# EPS_MPPT_Y_EMI-Filter_In.net
KiCad netlist of a schematic drawn in Altium Designer
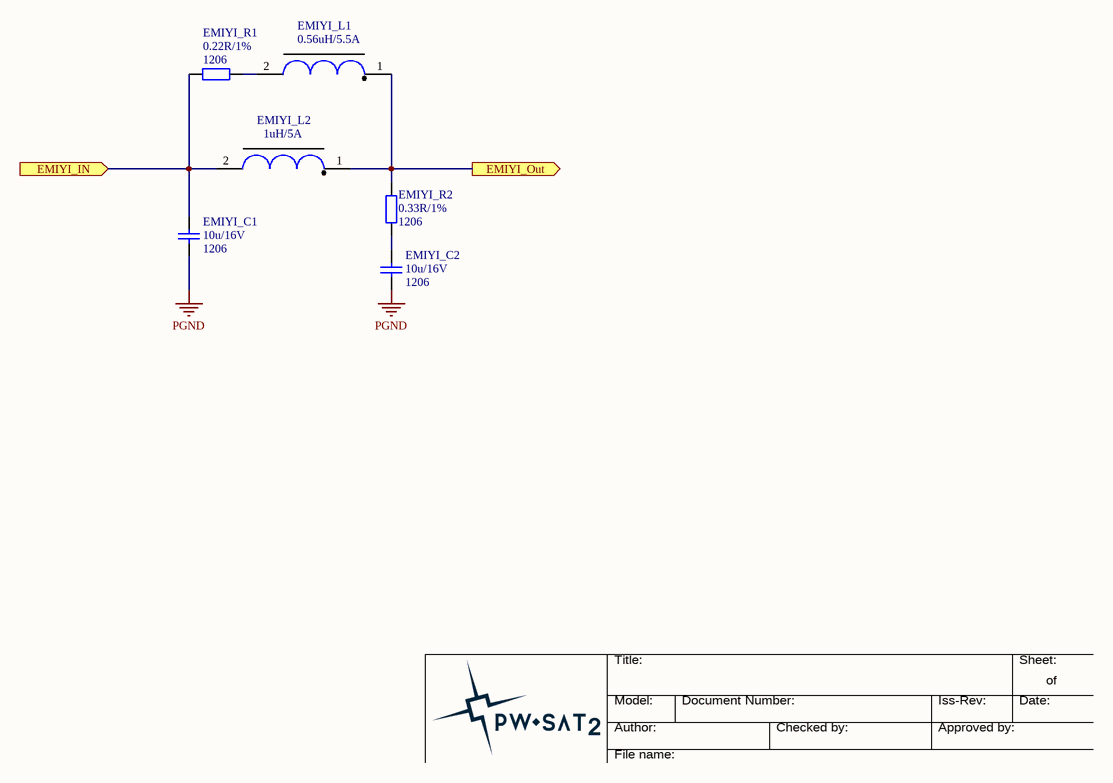
[diagram p0: EPS_MPPT_Y_EMI-Filter_In.SchDoc]

(export (version "E")
  (design (tool "Eeschema 10.0.6"))
  (components
    (comp (ref "EMIYI_C1")
      (value "10u/16V")
      (footprint "SMD_Capacitor_1206")
      (description "Ceramic Cap Kemet COTS 10u/16V X7R 1206")
      (fields
        (field (name "MANUFACTURERPARTNUMBER") "C1206T106K4RACTU")
        (field (name "MANUFACTURER") "Kemet")
        (field (name "PACKGE") "1206")
      )
      (libsource (lib "capacitors") (part "Cer_C1206T106K4RACTU"))
    )
    (comp (ref "EMIYI_C2")
      (value "10u/16V")
      (footprint "SMD_Capacitor_1206")
      (description "Ceramic Cap Kemet COTS 10u/16V X7R 1206")
      (fields
        (field (name "MANUFACTURERPARTNUMBER") "C1206T106K4RACTU")
        (field (name "MANUFACTURER") "Kemet")
        (field (name "PACKGE") "1206")
      )
      (libsource (lib "capacitors") (part "Cer_C1206T106K4RACTU"))
    )
    (comp (ref "EMIYI_L1")
      (value "0.56uH/5.5A")
      (footprint "Vishay_IHLP1212")
      (description "Vishay IHLP1212 Inductor, L=0.56uH, Irise40deg=5.5A, ESR=16mR, SRF=1MHz.")
      (fields
        (field (name "MANUFACTURER") "Vishay")
        (field (name "MANUFACTURERPARTNUMBER") "IHLP1212BZERR56M11")
      )
      (libsource (lib "inductors") (part "IHLP1212BZERR56M11"))
    )
    (comp (ref "EMIYI_L2")
      (value "1uH/5A")
      (footprint "Vishay_IHLP1212")
      (description "Vishay IHLP1212 Inductor, L=1uH, Irise40deg=5A, ESR=20mR, SRF=1MHz.")
      (fields
        (field (name "MANUFACTURER") "Vishay")
        (field (name "MANUFACTURERPARTNUMBER") "IHLP1212BZER1R0M11")
      )
      (libsource (lib "inductors") (part "IHLP1212BZER1R0M11"))
    )
    (comp (ref "EMIYI_R1")
      (value "0.22R/1%")
      (footprint "SMD_Resistor_1206")
      (description "Panasonic Resistor 0.22R 1% 1206 330mW")
      (fields
        (field (name "MANUFACTURER") "Panasonic")
        (field (name "MANUFACTURERPARTNUMBER") "ERJ-8BQFR22V")
        (field (name "PACKAGE") "1206")
      )
      (libsource (lib "resistors") (part "ERJ-8BQFR22V"))
    )
    (comp (ref "EMIYI_R2")
      (value "0.33R/1%")
      (footprint "SMD_Resistor_1206")
      (description "Panasonic Resistor 0.33R 1% 1206 330mW")
      (fields
        (field (name "MANUFACTURER") "Panasonic")
        (field (name "MANUFACTURERPARTNUMBER") "ERJ-8BQFR33V")
        (field (name "PACKAGE") "1206")
      )
      (libsource (lib "resistors") (part "ERJ-8BQFR33V"))
    )
  )
  (nets
    (net (code "1") (name "/EMIYI_IN") (class "Default")
      (node (ref "EMIYI_C1") (pin "1") (pinfunction "1_1") (pintype "passive"))
      (node (ref "EMIYI_L2") (pin "2") (pinfunction "2_2") (pintype "passive"))
      (node (ref "EMIYI_R1") (pin "1") (pinfunction "1_1") (pintype "passive"))
    )
    (net (code "2") (name "/EMIYI_Out") (class "Default")
      (node (ref "EMIYI_L1") (pin "1") (pinfunction "1_1") (pintype "passive"))
      (node (ref "EMIYI_L2") (pin "1") (pinfunction "1_1") (pintype "passive"))
      (node (ref "EMIYI_R2") (pin "2") (pinfunction "2_2") (pintype "passive"))
    )
    (net (code "3") (name "Net-(EMIYI_C2-Pad1)") (class "Default")
      (node (ref "EMIYI_C2") (pin "1") (pinfunction "1_1") (pintype "passive"))
      (node (ref "EMIYI_R2") (pin "1") (pinfunction "1_1") (pintype "passive"))
    )
    (net (code "4") (name "Net-(EMIYI_L1-Pad2)") (class "Default")
      (node (ref "EMIYI_L1") (pin "2") (pinfunction "2_2") (pintype "passive"))
      (node (ref "EMIYI_R1") (pin "2") (pinfunction "2_2") (pintype "passive"))
    )
    (net (code "5") (name "PGND") (class "Default")
      (node (ref "EMIYI_C1") (pin "2") (pinfunction "2_2") (pintype "passive"))
      (node (ref "EMIYI_C2") (pin "2") (pinfunction "2_2") (pintype "passive"))
    )
  )
)
